# Sheet4.net
KiCad netlist of a schematic drawn in Altium Designer
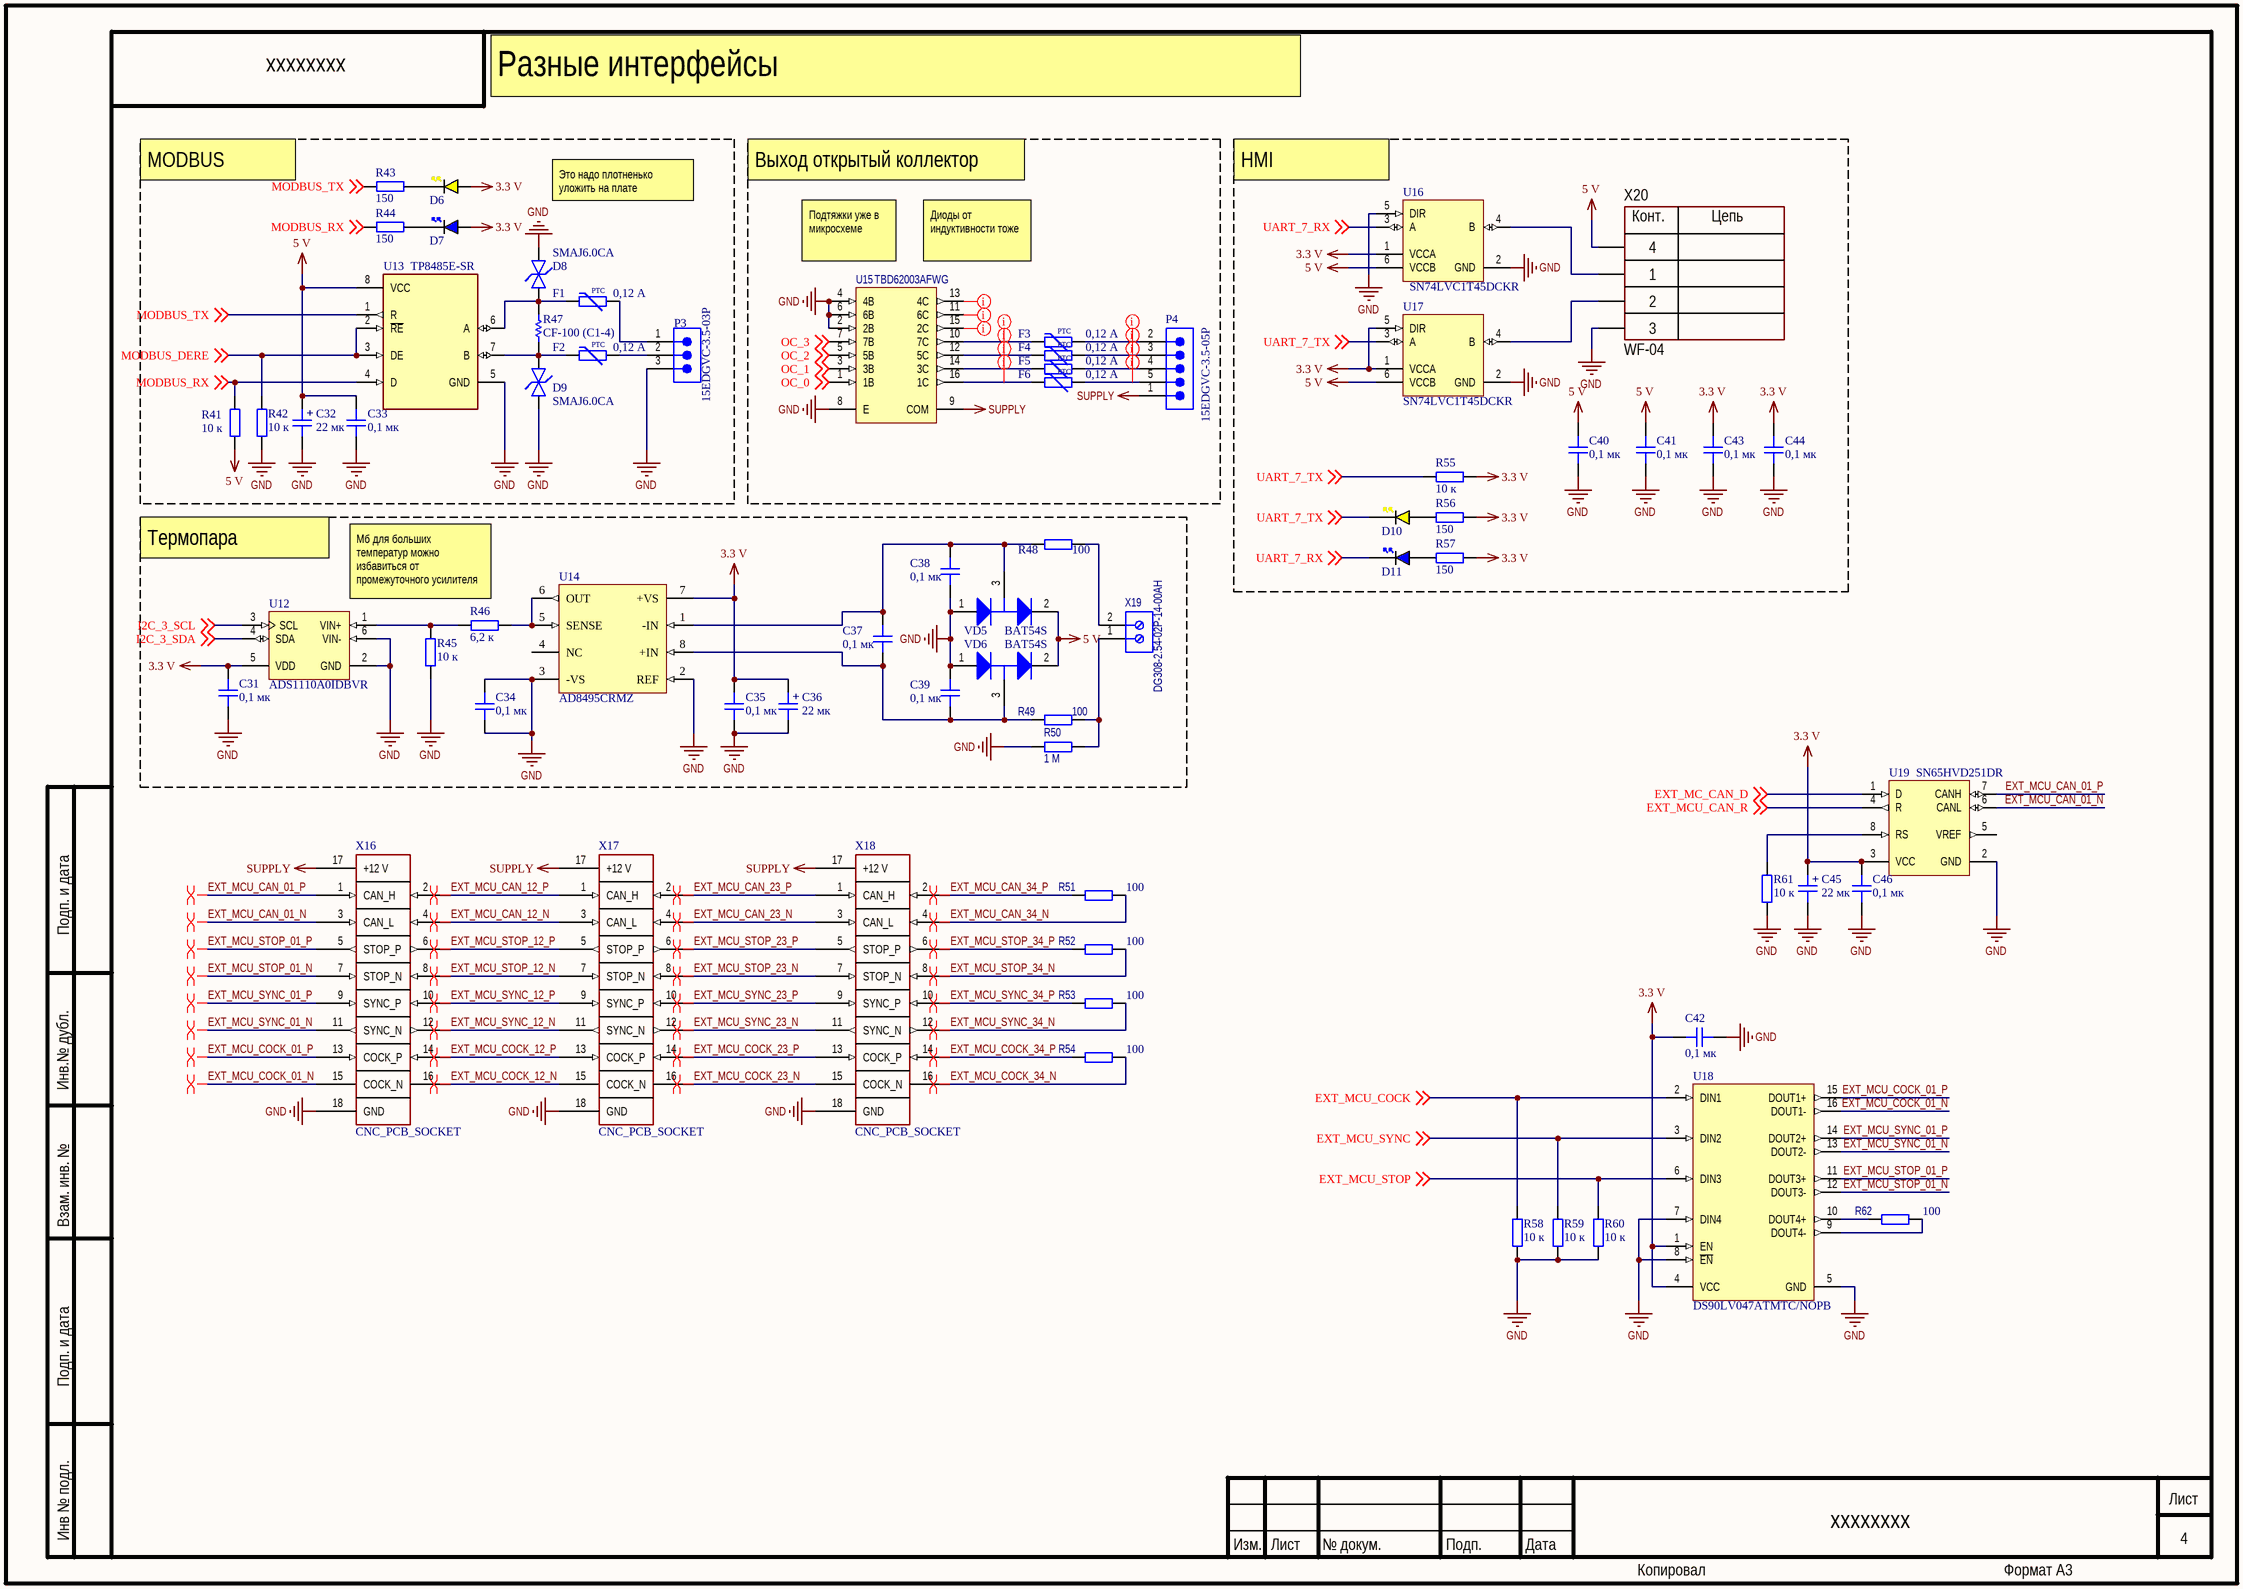
[diagram p0: Sheet4.SchDoc]

(export (version "E")
  (design (tool "Eeschema 10.0.6"))
  (components
    (comp (ref "C31")
      (value "0,1 мк")
      (footprint "CAP_0603")
      (description "Керамический конденсатор")
      (libsource (lib "Schematic-Lib-PhilsLab") (part "CAP_0603"))
    )
    (comp (ref "C32")
      (value "22 мк")
      (footprint "TANTAL_B")
      (description "Танталовый конденсатор")
      (fields (field (name "VOLTAGE") "6,3"))
      (libsource (lib "Schematic-Lib-PhilsLab") (part "CAP_ALEL_16x16.5_25V"))
    )
    (comp (ref "C33")
      (value "0,1 мк")
      (footprint "CAP_0603")
      (description "Керамический конденсатор")
      (libsource (lib "Schematic-Lib-PhilsLab") (part "CAP_0603"))
    )
    (comp (ref "C34")
      (value "0,1 мк")
      (footprint "CAP_0603")
      (description "Керамический конденсатор")
      (libsource (lib "Schematic-Lib-PhilsLab") (part "CAP_0603"))
    )
    (comp (ref "C35")
      (value "0,1 мк")
      (footprint "CAP_0603")
      (description "Керамический конденсатор")
      (libsource (lib "Schematic-Lib-PhilsLab") (part "CAP_0603"))
    )
    (comp (ref "C36")
      (value "22 мк")
      (footprint "TANTAL_B")
      (description "Танталовый конденсатор")
      (fields (field (name "VOLTAGE") "6,3"))
      (libsource (lib "Schematic-Lib-PhilsLab") (part "CAP_ALEL_16x16.5_25V"))
    )
    (comp (ref "C37")
      (value "0,1 мк")
      (footprint "CAP_0603")
      (description "Керамический конденсатор")
      (libsource (lib "Schematic-Lib-PhilsLab") (part "CAP_0603"))
    )
    (comp (ref "C38")
      (value "0,1 мк")
      (footprint "CAP_0603")
      (description "Керамический конденсатор")
      (libsource (lib "Schematic-Lib-PhilsLab") (part "CAP_0603"))
    )
    (comp (ref "C39")
      (value "0,1 мк")
      (footprint "CAP_0603")
      (description "Керамический конденсатор")
      (libsource (lib "Schematic-Lib-PhilsLab") (part "CAP_0603"))
    )
    (comp (ref "C40")
      (value "0,1 мк")
      (footprint "CAP_0603")
      (description "Керамический конденсатор")
      (libsource (lib "Schematic-Lib-PhilsLab") (part "CAP_0603"))
    )
    (comp (ref "C41")
      (value "0,1 мк")
      (footprint "CAP_0603")
      (description "Керамический конденсатор")
      (libsource (lib "Schematic-Lib-PhilsLab") (part "CAP_0603"))
    )
    (comp (ref "C42")
      (value "0,1 мк")
      (footprint "CAP_0603")
      (description "Керамический конденсатор")
      (libsource (lib "Schematic-Lib-PhilsLab") (part "CAP_0603"))
    )
    (comp (ref "C43")
      (value "0,1 мк")
      (footprint "CAP_0603")
      (description "Керамический конденсатор")
      (libsource (lib "Schematic-Lib-PhilsLab") (part "CAP_0603"))
    )
    (comp (ref "C44")
      (value "0,1 мк")
      (footprint "CAP_0603")
      (description "Керамический конденсатор")
      (libsource (lib "Schematic-Lib-PhilsLab") (part "CAP_0603"))
    )
    (comp (ref "C45")
      (value "22 мк")
      (footprint "TANTAL_B")
      (description "Танталовый конденсатор")
      (fields (field (name "VOLTAGE") "6,3"))
      (libsource (lib "Schematic-Lib-PhilsLab") (part "CAP_ALEL_16x16.5_25V"))
    )
    (comp (ref "C46")
      (value "0,1 мк")
      (footprint "CAP_0603")
      (description "Керамический конденсатор")
      (libsource (lib "Schematic-Lib-PhilsLab") (part "CAP_0603"))
    )
    (comp (ref "D6")
      (value "YELLOW")
      (footprint "LED_0603_YELLOW")
      (description "Жёлтый светодиод")
      (libsource (lib "Schematic-Lib-PhilsLab") (part "LED_0603_YELLOW"))
    )
    (comp (ref "D7")
      (value "BLUE")
      (footprint "LED_0603_BLUE")
      (description "Синий светодиод")
      (libsource (lib "Schematic-Lib-PhilsLab") (part "LED_0805_BLUE"))
    )
    (comp (ref "D8")
      (value "SMAJ6.0CA")
      (footprint "SMA")
      (description "Защитный диод")
      (libsource (lib "Schematic-Lib-PhilsLab") (part "D_TVS_BI_SMC"))
    )
    (comp (ref "D9")
      (value "SMAJ6.0CA")
      (footprint "SMA")
      (description "Защитный диод")
      (libsource (lib "Schematic-Lib-PhilsLab") (part "D_TVS_BI_SMC"))
    )
    (comp (ref "D10")
      (value "YELLOW")
      (footprint "LED_0603_YELLOW")
      (description "Жёлтый светодиод")
      (libsource (lib "Schematic-Lib-PhilsLab") (part "LED_0603_YELLOW"))
    )
    (comp (ref "D11")
      (value "BLUE")
      (footprint "LED_0603_BLUE")
      (description "Синий светодиод")
      (libsource (lib "Schematic-Lib-PhilsLab") (part "LED_0805_BLUE"))
    )
    (comp (ref "F1")
      (value "0,12 А")
      (footprint "FUSE_1206")
      (description "Самовосстанавливающийся предохранитель")
      (libsource (lib "Schematic-Lib-PhilsLab") (part "FUSE_PPTC_1206"))
    )
    (comp (ref "F2")
      (value "0,12 А")
      (footprint "FUSE_1206")
      (description "Самовосстанавливающийся предохранитель")
      (libsource (lib "Schematic-Lib-PhilsLab") (part "FUSE_PPTC_1206"))
    )
    (comp (ref "F3")
      (value "0,12 А")
      (footprint "FUSE_1206")
      (description "Самовосстанавливающийся предохранитель")
      (libsource (lib "Schematic-Lib-PhilsLab") (part "FUSE_PPTC_1206"))
    )
    (comp (ref "F4")
      (value "0,12 А")
      (footprint "FUSE_1206")
      (description "Самовосстанавливающийся предохранитель")
      (libsource (lib "Schematic-Lib-PhilsLab") (part "FUSE_PPTC_1206"))
    )
    (comp (ref "F5")
      (value "0,12 А")
      (footprint "FUSE_1206")
      (description "Самовосстанавливающийся предохранитель")
      (libsource (lib "Schematic-Lib-PhilsLab") (part "FUSE_PPTC_1206"))
    )
    (comp (ref "F6")
      (value "0,12 А")
      (footprint "FUSE_1206")
      (description "Самовосстанавливающийся предохранитель")
      (libsource (lib "Schematic-Lib-PhilsLab") (part "FUSE_PPTC_1206"))
    )
    (comp (ref "P3")
      (value "15EDGVC-3.5-03P")
      (footprint "691321100003")
      (description "Винтовой клеммник")
      (libsource (lib "Altium Content Vault") (part "TBL - 1R - 03P - Male"))
    )
    (comp (ref "P4")
      (value "15EDGVC-3.5-05P")
      (footprint "691321100005")
      (description "Винтовой клеммник")
      (libsource (lib "Altium Content Vault") (part "TBL - 1R - 05P - Male"))
    )
    (comp (ref "R41")
      (value "10 к")
      (footprint "RES_0603")
      (description "Резистор")
      (libsource (lib "Schematic-Lib-PhilsLab") (part "RES_0603"))
    )
    (comp (ref "R42")
      (value "10 к")
      (footprint "RES_0603")
      (description "Резистор")
      (libsource (lib "Schematic-Lib-PhilsLab") (part "RES_0603"))
    )
    (comp (ref "R43")
      (value "150")
      (footprint "RES_0603")
      (description "Резистор")
      (libsource (lib "Schematic-Lib-PhilsLab") (part "RES_0603"))
    )
    (comp (ref "R44")
      (value "150")
      (footprint "RES_0603")
      (description "Резистор")
      (libsource (lib "Schematic-Lib-PhilsLab") (part "RES_0603"))
    )
    (comp (ref "R45")
      (value "10 к")
      (footprint "RES_0603")
      (description "Резистор")
      (libsource (lib "Schematic-Lib-PhilsLab") (part "RES_0603"))
    )
    (comp (ref "R46")
      (value "6,2 к")
      (footprint "RES_0603")
      (description "Резистор")
      (libsource (lib "Schematic-Lib-PhilsLab") (part "RES_0603"))
    )
    (comp (ref "R47")
      (value "CF-100 (С1-4)")
      (footprint "OMTE-RES7X2.5-2")
      (description "Резистор")
      (libsource (lib "Altium Content Vault") (part "RES-2"))
    )
    (comp (ref "R48")
      (value "100")
      (footprint "RES_0603")
      (description "Резистор")
      (libsource (lib "Schematic-Lib-PhilsLab") (part "RES_0603"))
    )
    (comp (ref "R49")
      (value "100")
      (footprint "RES_0603")
      (description "Резистор")
      (libsource (lib "Schematic-Lib-PhilsLab") (part "RES_0603"))
    )
    (comp (ref "R50")
      (value "1 М")
      (footprint "RES_0603")
      (description "Резистор")
      (libsource (lib "Schematic-Lib-PhilsLab") (part "RES_0603"))
    )
    (comp (ref "R51")
      (value "100")
      (footprint "RES_0603")
      (description "Резистор")
      (libsource (lib "Schematic-Lib-PhilsLab") (part "RES_0603"))
    )
    (comp (ref "R52")
      (value "100")
      (footprint "RES_0603")
      (description "Резистор")
      (libsource (lib "Schematic-Lib-PhilsLab") (part "RES_0603"))
    )
    (comp (ref "R53")
      (value "100")
      (footprint "RES_0603")
      (description "Резистор")
      (libsource (lib "Schematic-Lib-PhilsLab") (part "RES_0603"))
    )
    (comp (ref "R54")
      (value "100")
      (footprint "RES_0603")
      (description "Резистор")
      (libsource (lib "Schematic-Lib-PhilsLab") (part "RES_0603"))
    )
    (comp (ref "R55")
      (value "10 к")
      (footprint "RES_0603")
      (description "Резистор")
      (libsource (lib "Schematic-Lib-PhilsLab") (part "RES_0603"))
    )
    (comp (ref "R56")
      (value "150")
      (footprint "RES_0603")
      (description "Резистор")
      (libsource (lib "Schematic-Lib-PhilsLab") (part "RES_0603"))
    )
    (comp (ref "R57")
      (value "150")
      (footprint "RES_0603")
      (description "Резистор")
      (libsource (lib "Schematic-Lib-PhilsLab") (part "RES_0603"))
    )
    (comp (ref "R58")
      (value "10 к")
      (footprint "RES_0603")
      (description "Резистор")
      (libsource (lib "Schematic-Lib-PhilsLab") (part "RES_0603"))
    )
    (comp (ref "R59")
      (value "10 к")
      (footprint "RES_0603")
      (description "Резистор")
      (libsource (lib "Schematic-Lib-PhilsLab") (part "RES_0603"))
    )
    (comp (ref "R60")
      (value "10 к")
      (footprint "RES_0603")
      (description "Резистор")
      (libsource (lib "Schematic-Lib-PhilsLab") (part "RES_0603"))
    )
    (comp (ref "R61")
      (value "10 к")
      (footprint "RES_0603")
      (description "Резистор")
      (libsource (lib "Schematic-Lib-PhilsLab") (part "RES_0603"))
    )
    (comp (ref "R62")
      (value "100")
      (footprint "RES_0603")
      (description "Резистор")
      (libsource (lib "Schematic-Lib-PhilsLab") (part "RES_0603"))
    )
    (comp (ref "U12")
      (value "ADS1110A0IDBVR")
      (footprint "TI-DBV6_M")
      (description "АЦП с I2C")
      (libsource (lib "Altium Content Vault") (part "TI-ADS1XX0XDBV6"))
    )
    (comp (ref "U13")
      (value "TP8485E-SR")
      (footprint "FP-D0008A-MFG")
      (description "Конвертер UART <-> RS485")
      (libsource (lib "Altium Content Vault") (part "091f02ab22138f139970934c9fc963e"))
    )
    (comp (ref "U14")
      (value "AD8495CRMZ")
      (footprint "FP-RM-8-IPC_A")
      (description "Усилитель термопары")
      (libsource (lib "Altium Content Vault") (part "AD8495CRMZ"))
    )
    (comp (ref "U15")
      (value "TBD62003AFWG")
      (footprint "D0016A_M")
      (description "Сборка транзисторов Дарлингтона")
      (libsource (lib "Altium Content Vault") (part "TI-ULX200X-D-16"))
    )
    (comp (ref "U16")
      (value "SN74LVC1T45DCKR")
      (footprint "DCK0006A_L")
      (description "Конвертер уровней")
      (libsource (lib "Altium Content Vault") (part "TI-SN74XVC1T45-6"))
    )
    (comp (ref "U17")
      (value "SN74LVC1T45DCKR")
      (footprint "DCK0006A_L")
      (description "Конвертер уровней")
      (libsource (lib "Altium Content Vault") (part "TI-SN74XVC1T45-6"))
    )
    (comp (ref "U18")
      (value "DS90LV047ATMTC/NOPB")
      (footprint "MTC16_M")
      (description "Драйвер LVDS")
      (libsource (lib "Altium Content Vault") (part "IN-LNDRV-DS90LV047ATM"))
    )
    (comp (ref "U19")
      (value "SN65HVD251DR")
      (footprint "D0008A_N")
      (description "Драйвер CAN")
      (libsource (lib "Altium Content Vault") (part "TI-SN65HVD251-SOIC_D-8"))
    )
    (comp (ref "VD5")
      (value "BAT54S")
      (footprint "ONSC-SOT-323-3-419-04_V")
      (description "Пара последовательных диодов")
      (libsource (lib "Altium Content Vault") (part "ONSC-D-A1K2C3-3"))
    )
    (comp (ref "VD6")
      (value "BAT54S")
      (footprint "ONSC-SOT-323-3-419-04_V")
      (description "Пара последовательных диодов")
      (libsource (lib "Altium Content Vault") (part "ONSC-D-A1K2C3-3"))
    )
    (comp (ref "X16")
      (value "CNC_PCB_SOCKET")
      (footprint "CNC_PCB_SOCKET")
      (libsource (lib "BarkockLib") (part "CNC_PCB_SOCKET"))
    )
    (comp (ref "X17")
      (value "CNC_PCB_SOCKET")
      (footprint "CNC_PCB_SOCKET")
      (libsource (lib "BarkockLib") (part "CNC_PCB_SOCKET"))
    )
    (comp (ref "X18")
      (value "CNC_PCB_SOCKET")
      (footprint "CNC_PCB_SOCKET")
      (libsource (lib "BarkockLib") (part "CNC_PCB_SOCKET"))
    )
    (comp (ref "X19")
      (value "DG308-2.54-02P-14-00AH")
      (footprint "PHOE-1725656-2")
      (description "Рахъёмный винтовой клеммник")
      (libsource (lib "Altium Content Vault") (part "CN-1P-F-TB2"))
    )
    (comp (ref "X20")
      (value "WF-04")
      (footprint "CON: WF-04")
      (description "Штыревой разъём")
      (libsource (lib "Connectors") (part "4-Connector"))
    )
  )
  (nets
    (net (code "1") (name "/EXT_MCU_CAN_01_N") (class "Default")
      (node (ref "U19") (pin "6") (pinfunction "CANL_6") (pintype "bidirectional"))
      (node (ref "X16") (pin "3") (pinfunction "CAN_L_3") (pintype "input"))
    )
    (net (code "2") (name "/EXT_MCU_CAN_01_P") (class "Default")
      (node (ref "U19") (pin "7") (pinfunction "CANH_7") (pintype "bidirectional"))
      (node (ref "X16") (pin "1") (pinfunction "CAN_H_1") (pintype "input"))
    )
    (net (code "3") (name "/EXT_MCU_CAN_12_N") (class "Default")
      (node (ref "X16") (pin "4") (pinfunction "CAN_L_4") (pintype "input"))
      (node (ref "X17") (pin "3") (pinfunction "CAN_L_3") (pintype "input"))
    )
    (net (code "4") (name "/EXT_MCU_CAN_12_P") (class "Default")
      (node (ref "X16") (pin "2") (pinfunction "CAN_H_2") (pintype "input"))
      (node (ref "X17") (pin "1") (pinfunction "CAN_H_1") (pintype "input"))
    )
    (net (code "5") (name "/EXT_MCU_CAN_23_N") (class "Default")
      (node (ref "X17") (pin "4") (pinfunction "CAN_L_4") (pintype "input"))
      (node (ref "X18") (pin "3") (pinfunction "CAN_L_3") (pintype "input"))
    )
    (net (code "6") (name "/EXT_MCU_CAN_23_P") (class "Default")
      (node (ref "X17") (pin "2") (pinfunction "CAN_H_2") (pintype "input"))
      (node (ref "X18") (pin "1") (pinfunction "CAN_H_1") (pintype "input"))
    )
    (net (code "7") (name "/EXT_MCU_CAN_34_N") (class "Default")
      (node (ref "R51") (pin "1") (pinfunction "1_1") (pintype "passive"))
      (node (ref "X18") (pin "4") (pinfunction "CAN_L_4") (pintype "input"))
    )
    (net (code "8") (name "/EXT_MCU_CAN_34_P") (class "Default")
      (node (ref "R51") (pin "2") (pinfunction "2_2") (pintype "passive"))
      (node (ref "X18") (pin "2") (pinfunction "CAN_H_2") (pintype "input"))
    )
    (net (code "9") (name "/EXT_MCU_COCK_01_N") (class "Default")
      (node (ref "U18") (pin "16") (pinfunction "DOUT1-_16") (pintype "output"))
      (node (ref "X16") (pin "15") (pinfunction "COCK_N_15") (pintype "power_in"))
    )
    (net (code "10") (name "/EXT_MCU_COCK_01_P") (class "Default")
      (node (ref "U18") (pin "15") (pinfunction "DOUT1+_15") (pintype "output"))
      (node (ref "X16") (pin "13") (pinfunction "COCK_P_13") (pintype "input"))
    )
    (net (code "11") (name "/EXT_MCU_COCK_12_N") (class "Default")
      (node (ref "X16") (pin "16") (pinfunction "COCK_N_16") (pintype "power_in"))
      (node (ref "X17") (pin "15") (pinfunction "COCK_N_15") (pintype "power_in"))
    )
    (net (code "12") (name "/EXT_MCU_COCK_12_P") (class "Default")
      (node (ref "X16") (pin "14") (pinfunction "COCK_P_14") (pintype "input"))
      (node (ref "X17") (pin "13") (pinfunction "COCK_P_13") (pintype "input"))
    )
    (net (code "13") (name "/EXT_MCU_COCK_23_N") (class "Default")
      (node (ref "X17") (pin "16") (pinfunction "COCK_N_16") (pintype "power_in"))
      (node (ref "X18") (pin "15") (pinfunction "COCK_N_15") (pintype "power_in"))
    )
    (net (code "14") (name "/EXT_MCU_COCK_23_P") (class "Default")
      (node (ref "X17") (pin "14") (pinfunction "COCK_P_14") (pintype "input"))
      (node (ref "X18") (pin "13") (pinfunction "COCK_P_13") (pintype "input"))
    )
    (net (code "15") (name "/EXT_MCU_COCK_34_N") (class "Default")
      (node (ref "R54") (pin "1") (pinfunction "1_1") (pintype "passive"))
      (node (ref "X18") (pin "16") (pinfunction "COCK_N_16") (pintype "power_in"))
    )
    (net (code "16") (name "/EXT_MCU_COCK_34_P") (class "Default")
      (node (ref "R54") (pin "2") (pinfunction "2_2") (pintype "passive"))
      (node (ref "X18") (pin "14") (pinfunction "COCK_P_14") (pintype "input"))
    )
    (net (code "17") (name "/EXT_MCU_STOP_01_N") (class "Default")
      (node (ref "U18") (pin "12") (pinfunction "DOUT3-_12") (pintype "output"))
      (node (ref "X16") (pin "7") (pinfunction "STOP_N_7") (pintype "input"))
    )
    (net (code "18") (name "/EXT_MCU_STOP_01_P") (class "Default")
      (node (ref "U18") (pin "11") (pinfunction "DOUT3+_11") (pintype "output"))
      (node (ref "X16") (pin "5") (pinfunction "STOP_P_5") (pintype "output"))
    )
    (net (code "19") (name "/EXT_MCU_STOP_12_N") (class "Default")
      (node (ref "X16") (pin "8") (pinfunction "STOP_N_8") (pintype "input"))
      (node (ref "X17") (pin "7") (pinfunction "STOP_N_7") (pintype "input"))
    )
    (net (code "20") (name "/EXT_MCU_STOP_12_P") (class "Default")
      (node (ref "X16") (pin "6") (pinfunction "STOP_P_6") (pintype "output"))
      (node (ref "X17") (pin "5") (pinfunction "STOP_P_5") (pintype "output"))
    )
    (net (code "21") (name "/EXT_MCU_STOP_23_N") (class "Default")
      (node (ref "X17") (pin "8") (pinfunction "STOP_N_8") (pintype "input"))
      (node (ref "X18") (pin "7") (pinfunction "STOP_N_7") (pintype "input"))
    )
    (net (code "22") (name "/EXT_MCU_STOP_23_P") (class "Default")
      (node (ref "X17") (pin "6") (pinfunction "STOP_P_6") (pintype "output"))
      (node (ref "X18") (pin "5") (pinfunction "STOP_P_5") (pintype "output"))
    )
    (net (code "23") (name "/EXT_MCU_STOP_34_N") (class "Default")
      (node (ref "R52") (pin "1") (pinfunction "1_1") (pintype "passive"))
      (node (ref "X18") (pin "8") (pinfunction "STOP_N_8") (pintype "input"))
    )
    (net (code "24") (name "/EXT_MCU_STOP_34_P") (class "Default")
      (node (ref "R52") (pin "2") (pinfunction "2_2") (pintype "passive"))
      (node (ref "X18") (pin "6") (pinfunction "STOP_P_6") (pintype "output"))
    )
    (net (code "25") (name "/EXT_MCU_SYNC_01_N") (class "Default")
      (node (ref "U18") (pin "13") (pinfunction "DOUT2-_13") (pintype "output"))
      (node (ref "X16") (pin "11") (pinfunction "SYNC_N_11") (pintype "output"))
    )
    (net (code "26") (name "/EXT_MCU_SYNC_01_P") (class "Default")
      (node (ref "U18") (pin "14") (pinfunction "DOUT2+_14") (pintype "output"))
      (node (ref "X16") (pin "9") (pinfunction "SYNC_P_9") (pintype "input"))
    )
    (net (code "27") (name "/EXT_MCU_SYNC_12_N") (class "Default")
      (node (ref "X16") (pin "12") (pinfunction "SYNC_N_12") (pintype "output"))
      (node (ref "X17") (pin "11") (pinfunction "SYNC_N_11") (pintype "output"))
    )
    (net (code "28") (name "/EXT_MCU_SYNC_12_P") (class "Default")
      (node (ref "X16") (pin "10") (pinfunction "SYNC_P_10") (pintype "input"))
      (node (ref "X17") (pin "9") (pinfunction "SYNC_P_9") (pintype "input"))
    )
    (net (code "29") (name "/EXT_MCU_SYNC_23_N") (class "Default")
      (node (ref "X17") (pin "12") (pinfunction "SYNC_N_12") (pintype "output"))
      (node (ref "X18") (pin "11") (pinfunction "SYNC_N_11") (pintype "output"))
    )
    (net (code "30") (name "/EXT_MCU_SYNC_23_P") (class "Default")
      (node (ref "X17") (pin "10") (pinfunction "SYNC_P_10") (pintype "input"))
      (node (ref "X18") (pin "9") (pinfunction "SYNC_P_9") (pintype "input"))
    )
    (net (code "31") (name "/EXT_MCU_SYNC_34_N") (class "Default")
      (node (ref "R53") (pin "1") (pinfunction "1_1") (pintype "passive"))
      (node (ref "X18") (pin "12") (pinfunction "SYNC_N_12") (pintype "output"))
    )
    (net (code "32") (name "/EXT_MCU_SYNC_34_P") (class "Default")
      (node (ref "R53") (pin "2") (pinfunction "2_2") (pintype "passive"))
      (node (ref "X18") (pin "10") (pinfunction "SYNC_P_10") (pintype "input"))
    )
    (net (code "33") (name "3.3 V") (class "Default")
      (node (ref "C31") (pin "1") (pinfunction "1_1") (pintype "passive"))
      (node (ref "C35") (pin "1") (pinfunction "1_1") (pintype "passive"))
      (node (ref "C36") (pin "1") (pinfunction "1_1") (pintype "passive"))
      (node (ref "C42") (pin "1") (pinfunction "1_1") (pintype "passive"))
      (node (ref "C43") (pin "1") (pinfunction "1_1") (pintype "passive"))
      (node (ref "C44") (pin "1") (pinfunction "1_1") (pintype "passive"))
      (node (ref "C45") (pin "1") (pinfunction "1_1") (pintype "passive"))
      (node (ref "C46") (pin "1") (pinfunction "1_1") (pintype "passive"))
      (node (ref "D6") (pin "A") (pinfunction "A_A") (pintype "passive"))
      (node (ref "D7") (pin "A") (pinfunction "A_A") (pintype "passive"))
      (node (ref "R55") (pin "1") (pinfunction "1_1") (pintype "passive"))
      (node (ref "R56") (pin "2") (pinfunction "2_2") (pintype "passive"))
      (node (ref "R57") (pin "2") (pinfunction "2_2") (pintype "passive"))
      (node (ref "U12") (pin "5") (pinfunction "VDD_5") (pintype "power_in"))
      (node (ref "U14") (pin "7") (pinfunction "+VS_7") (pintype "power_in"))
      (node (ref "U16") (pin "1") (pinfunction "VCCA_1") (pintype "power_in"))
      (node (ref "U17") (pin "1") (pinfunction "VCCA_1") (pintype "power_in"))
      (node (ref "U17") (pin "5") (pinfunction "DIR_5") (pintype "input"))
      (node (ref "U18") (pin "1") (pinfunction "EN_1") (pintype "input"))
      (node (ref "U18") (pin "4") (pinfunction "VCC_4") (pintype "power_in"))
      (node (ref "U19") (pin "3") (pinfunction "VCC_3") (pintype "power_in"))
    )
    (net (code "34") (name "5 V") (class "Default")
      (node (ref "C32") (pin "1") (pinfunction "1_1") (pintype "passive"))
      (node (ref "C33") (pin "1") (pinfunction "1_1") (pintype "passive"))
      (node (ref "C40") (pin "1") (pinfunction "1_1") (pintype "passive"))
      (node (ref "C41") (pin "1") (pinfunction "1_1") (pintype "passive"))
      (node (ref "R41") (pin "2") (pinfunction "2_2") (pintype "passive"))
      (node (ref "U13") (pin "8") (pinfunction "VCC_8") (pintype "power_in"))
      (node (ref "U16") (pin "6") (pinfunction "VCCB_6") (pintype "power_in"))
      (node (ref "U17") (pin "6") (pinfunction "VCCB_6") (pintype "power_in"))
      (node (ref "VD5") (pin "2") (pinfunction "K_2") (pintype "passive"))
      (node (ref "VD6") (pin "2") (pinfunction "K_2") (pintype "passive"))
      (node (ref "X20") (pin "4") (pinfunction "4_4") (pintype "passive"))
    )
    (net (code "35") (name "EXT_MCU_CAN_R") (class "Default")
      (node (ref "U19") (pin "4") (pinfunction "R_4") (pintype "output"))
    )
    (net (code "36") (name "EXT_MCU_COCK") (class "Default")
      (node (ref "R58") (pin "1") (pinfunction "1_1") (pintype "passive"))
      (node (ref "U18") (pin "2") (pinfunction "DIN1_2") (pintype "input"))
    )
    (net (code "37") (name "EXT_MCU_STOP") (class "Default")
      (node (ref "R60") (pin "2") (pinfunction "2_2") (pintype "passive"))
      (node (ref "U18") (pin "6") (pinfunction "DIN3_6") (pintype "input"))
    )
    (net (code "38") (name "EXT_MCU_SYNC") (class "Default")
      (node (ref "R59") (pin "1") (pinfunction "1_1") (pintype "passive"))
      (node (ref "U18") (pin "3") (pinfunction "DIN2_3") (pintype "input"))
    )
    (net (code "39") (name "EXT_MC_CAN_D") (class "Default")
      (node (ref "U19") (pin "1") (pinfunction "D_1") (pintype "input"))
    )
    (net (code "40") (name "GND") (class "Default")
      (node (ref "C31") (pin "2") (pinfunction "2_2") (pintype "passive"))
      (node (ref "C32") (pin "2") (pinfunction "2_2") (pintype "passive"))
      (node (ref "C33") (pin "2") (pinfunction "2_2") (pintype "passive"))
      (node (ref "C34") (pin "1") (pinfunction "1_1") (pintype "passive"))
      (node (ref "C34") (pin "2") (pinfunction "2_2") (pintype "passive"))
      (node (ref "C35") (pin "2") (pinfunction "2_2") (pintype "passive"))
      (node (ref "C36") (pin "2") (pinfunction "2_2") (pintype "passive"))
      (node (ref "C38") (pin "2") (pinfunction "2_2") (pintype "passive"))
      (node (ref "C39") (pin "1") (pinfunction "1_1") (pintype "passive"))
      (node (ref "C40") (pin "2") (pinfunction "2_2") (pintype "passive"))
      (node (ref "C41") (pin "2") (pinfunction "2_2") (pintype "passive"))
      (node (ref "C42") (pin "2") (pinfunction "2_2") (pintype "passive"))
      (node (ref "C43") (pin "2") (pinfunction "2_2") (pintype "passive"))
      (node (ref "C44") (pin "2") (pinfunction "2_2") (pintype "passive"))
      (node (ref "C45") (pin "2") (pinfunction "2_2") (pintype "passive"))
      (node (ref "C46") (pin "2") (pinfunction "2_2") (pintype "passive"))
      (node (ref "D8") (pin "K") (pinfunction "K_K") (pintype "passive"))
      (node (ref "D9") (pin "A") (pinfunction "A_A") (pintype "passive"))
      (node (ref "P3") (pin "3") (pinfunction "3_3") (pintype "passive"))
      (node (ref "R42") (pin "1") (pinfunction "1_1") (pintype "passive"))
      (node (ref "R45") (pin "1") (pinfunction "1_1") (pintype "passive"))
      (node (ref "R50") (pin "2") (pinfunction "2_2") (pintype "passive"))
      (node (ref "R58") (pin "2") (pinfunction "2_2") (pintype "passive"))
      (node (ref "R59") (pin "2") (pinfunction "2_2") (pintype "passive"))
      (node (ref "R60") (pin "1") (pinfunction "1_1") (pintype "passive"))
      (node (ref "R61") (pin "1") (pinfunction "1_1") (pintype "passive"))
      (node (ref "U12") (pin "2") (pinfunction "GND_2") (pintype "power_in"))
      (node (ref "U12") (pin "6") (pinfunction "VIN-_6") (pintype "input"))
      (node (ref "U13") (pin "5") (pinfunction "GND_5") (pintype "power_in"))
      (node (ref "U14") (pin "2") (pinfunction "REF_2") (pintype "input"))
      (node (ref "U14") (pin "3") (pinfunction "-VS_3") (pintype "power_in"))
      (node (ref "U15") (pin "2") (pinfunction "2B_2") (pintype "input"))
      (node (ref "U15") (pin "4") (pinfunction "4B_4") (pintype "input"))
      (node (ref "U15") (pin "6") (pinfunction "6B_6") (pintype "input"))
      (node (ref "U15") (pin "8") (pinfunction "E_8") (pintype "passive"))
      (node (ref "U16") (pin "2") (pinfunction "GND_2") (pintype "power_in"))
      (node (ref "U16") (pin "5") (pinfunction "DIR_5") (pintype "input"))
      (node (ref "U17") (pin "2") (pinfunction "GND_2") (pintype "power_in"))
      (node (ref "U18") (pin "5") (pinfunction "GND_5") (pintype "power_in"))
      (node (ref "U18") (pin "7") (pinfunction "DIN4_7") (pintype "input"))
      (node (ref "U18") (pin "8") (pinfunction "~{EN}_8") (pintype "input"))
      (node (ref "U19") (pin "2") (pinfunction "GND_2") (pintype "power_in"))
      (node (ref "VD5") (pin "1") (pinfunction "A_1") (pintype "passive"))
      (node (ref "VD6") (pin "1") (pinfunction "A_1") (pintype "passive"))
      (node (ref "X16") (pin "18") (pinfunction "GND_18") (pintype "power_in"))
      (node (ref "X17") (pin "18") (pinfunction "GND_18") (pintype "power_in"))
      (node (ref "X18") (pin "18") (pinfunction "GND_18") (pintype "power_in"))
      (node (ref "X20") (pin "3") (pinfunction "3_3") (pintype "power_in"))
    )
    (net (code "41") (name "I2C_3_SCL") (class "Default")
      (node (ref "U12") (pin "3") (pinfunction "SCL_3") (pintype "input"))
    )
    (net (code "42") (name "I2C_3_SDA") (class "Default")
      (node (ref "U12") (pin "4") (pinfunction "SDA_4") (pintype "bidirectional"))
    )
    (net (code "43") (name "MODBUS_DERE") (class "Default")
      (node (ref "R42") (pin "2") (pinfunction "2_2") (pintype "passive"))
      (node (ref "U13") (pin "2") (pinfunction "~{RE}_2") (pintype "input"))
      (node (ref "U13") (pin "3") (pinfunction "DE_3") (pintype "input"))
    )
    (net (code "44") (name "MODBUS_RX") (class "Default")
      (node (ref "R41") (pin "1") (pinfunction "1_1") (pintype "passive"))
      (node (ref "R44") (pin "1") (pinfunction "1_1") (pintype "passive"))
      (node (ref "U13") (pin "4") (pinfunction "D_4") (pintype "input"))
    )
    (net (code "45") (name "MODBUS_TX") (class "Default")
      (node (ref "R43") (pin "1") (pinfunction "1_1") (pintype "passive"))
      (node (ref "U13") (pin "1") (pinfunction "R_1") (pintype "output"))
    )
    (net (code "46") (name "Net-(D6-PadK)") (class "Default")
      (node (ref "D6") (pin "K") (pinfunction "K_K") (pintype "passive"))
      (node (ref "R43") (pin "2") (pinfunction "2_2") (pintype "passive"))
    )
    (net (code "47") (name "Net-(D7-PadK)") (class "Default")
      (node (ref "D7") (pin "K") (pinfunction "K_K") (pintype "passive"))
      (node (ref "R44") (pin "2") (pinfunction "2_2") (pintype "passive"))
    )
    (net (code "48") (name "Net-(D10-PadA)") (class "Default")
      (node (ref "D10") (pin "A") (pinfunction "A_A") (pintype "passive"))
      (node (ref "R56") (pin "1") (pinfunction "1_1") (pintype "passive"))
    )
    (net (code "49") (name "Net-(D11-PadA)") (class "Default")
      (node (ref "D11") (pin "A") (pinfunction "A_A") (pintype "passive"))
      (node (ref "R57") (pin "1") (pinfunction "1_1") (pintype "passive"))
    )
    (net (code "50") (name "Net-(F1-Pad1)") (class "Default")
      (node (ref "F1") (pin "1") (pinfunction "1_1") (pintype "passive"))
      (node (ref "P3") (pin "1") (pinfunction "1_1") (pintype "passive"))
    )
    (net (code "51") (name "Net-(F2-Pad1)") (class "Default")
      (node (ref "F2") (pin "1") (pinfunction "1_1") (pintype "passive"))
      (node (ref "P3") (pin "2") (pinfunction "2_2") (pintype "passive"))
    )
    (net (code "52") (name "Net-(F3-Pad1)") (class "Default")
      (node (ref "F3") (pin "1") (pinfunction "1_1") (pintype "passive"))
      (node (ref "P4") (pin "2") (pinfunction "2_2") (pintype "passive"))
    )
    (net (code "53") (name "Net-(F4-Pad1)") (class "Default")
      (node (ref "F4") (pin "1") (pinfunction "1_1") (pintype "passive"))
      (node (ref "P4") (pin "3") (pinfunction "3_3") (pintype "passive"))
    )
    (net (code "54") (name "Net-(F5-Pad1)") (class "Default")
      (node (ref "F5") (pin "1") (pinfunction "1_1") (pintype "passive"))
      (node (ref "P4") (pin "4") (pinfunction "4_4") (pintype "passive"))
    )
    (net (code "55") (name "Net-(F6-Pad1)") (class "Default")
      (node (ref "F6") (pin "1") (pinfunction "1_1") (pintype "passive"))
      (node (ref "P4") (pin "5") (pinfunction "5_5") (pintype "passive"))
    )
    (net (code "56") (name "Net-(R48-Pad2)") (class "Default")
      (node (ref "R48") (pin "2") (pinfunction "2_2") (pintype "passive"))
      (node (ref "X19") (pin "2") (pinfunction "2_2") (pintype "passive"))
    )
    (net (code "57") (name "Net-(R49-Pad2)") (class "Default")
      (node (ref "R49") (pin "2") (pinfunction "2_2") (pintype "passive"))
      (node (ref "R50") (pin "1") (pinfunction "1_1") (pintype "passive"))
      (node (ref "X19") (pin "1") (pinfunction "1_1") (pintype "passive"))
    )
    (net (code "58") (name "Net-(U12-VIN+)") (class "Default")
      (node (ref "R45") (pin "2") (pinfunction "2_2") (pintype "passive"))
      (node (ref "R46") (pin "2") (pinfunction "2_2") (pintype "passive"))
      (node (ref "U12") (pin "1") (pinfunction "VIN+_1") (pintype "input"))
    )
    (net (code "59") (name "Net-(U13-A)") (class "Default")
      (node (ref "D8") (pin "A") (pinfunction "A_A") (pintype "passive"))
      (node (ref "F1") (pin "2") (pinfunction "2_2") (pintype "passive"))
      (node (ref "R47") (pin "1") (pinfunction "1_1") (pintype "passive"))
      (node (ref "U13") (pin "6") (pinfunction "A_6") (pintype "bidirectional"))
    )
    (net (code "60") (name "Net-(U13-B)") (class "Default")
      (node (ref "D9") (pin "K") (pinfunction "K_K") (pintype "passive"))
      (node (ref "F2") (pin "2") (pinfunction "2_2") (pintype "passive"))
      (node (ref "R47") (pin "2") (pinfunction "2_2") (pintype "passive"))
      (node (ref "U13") (pin "7") (pinfunction "B_7") (pintype "bidirectional"))
    )
    (net (code "61") (name "Net-(U14-+IN)") (class "Default")
      (node (ref "C37") (pin "2") (pinfunction "2_2") (pintype "passive"))
      (node (ref "C39") (pin "2") (pinfunction "2_2") (pintype "passive"))
      (node (ref "R49") (pin "1") (pinfunction "1_1") (pintype "passive"))
      (node (ref "U14") (pin "8") (pinfunction "+IN_8") (pintype "input"))
      (node (ref "VD6") (pin "3") (pinfunction "K/A_3") (pintype "passive"))
    )
    (net (code "62") (name "Net-(U14--IN)") (class "Default")
      (node (ref "C37") (pin "1") (pinfunction "1_1") (pintype "passive"))
      (node (ref "C38") (pin "1") (pinfunction "1_1") (pintype "passive"))
      (node (ref "R48") (pin "1") (pinfunction "1_1") (pintype "passive"))
      (node (ref "U14") (pin "1") (pinfunction "-IN_1") (pintype "input"))
      (node (ref "VD5") (pin "3") (pinfunction "K/A_3") (pintype "passive"))
    )
    (net (code "63") (name "Net-(U14-OUT)") (class "Default")
      (node (ref "R46") (pin "1") (pinfunction "1_1") (pintype "passive"))
      (node (ref "U14") (pin "5") (pinfunction "SENSE_5") (pintype "input"))
      (node (ref "U14") (pin "6") (pinfunction "OUT_6") (pintype "output"))
    )
    (net (code "64") (name "Net-(U15-1C)") (class "Default")
      (node (ref "F6") (pin "2") (pinfunction "2_2") (pintype "passive"))
      (node (ref "U15") (pin "16") (pinfunction "1C_16") (pintype "output"))
    )
    (net (code "65") (name "Net-(U15-3C)") (class "Default")
      (node (ref "F5") (pin "2") (pinfunction "2_2") (pintype "passive"))
      (node (ref "U15") (pin "14") (pinfunction "3C_14") (pintype "output"))
    )
    (net (code "66") (name "Net-(U15-5C)") (class "Default")
      (node (ref "F4") (pin "2") (pinfunction "2_2") (pintype "passive"))
      (node (ref "U15") (pin "12") (pinfunction "5C_12") (pintype "output"))
    )
    (net (code "67") (name "Net-(U15-7C)") (class "Default")
      (node (ref "F3") (pin "2") (pinfunction "2_2") (pintype "passive"))
      (node (ref "U15") (pin "10") (pinfunction "7C_10") (pintype "output"))
    )
    (net (code "68") (name "Net-(U16-B)") (class "Default")
      (node (ref "U16") (pin "4") (pinfunction "B_4") (pintype "bidirectional"))
      (node (ref "X20") (pin "1") (pinfunction "1_1") (pintype "passive"))
    )
    (net (code "69") (name "Net-(U17-B)") (class "Default")
      (node (ref "U17") (pin "4") (pinfunction "B_4") (pintype "bidirectional"))
      (node (ref "X20") (pin "2") (pinfunction "2_2") (pintype "power_in"))
    )
    (net (code "70") (name "Net-(U18-DOUT4+)") (class "Default")
      (node (ref "R62") (pin "2") (pinfunction "2_2") (pintype "passive"))
      (node (ref "U18") (pin "10") (pinfunction "DOUT4+_10") (pintype "output"))
    )
    (net (code "71") (name "Net-(U18-DOUT4-)") (class "Default")
      (node (ref "R62") (pin "1") (pinfunction "1_1") (pintype "passive"))
      (node (ref "U18") (pin "9") (pinfunction "DOUT4-_9") (pintype "output"))
    )
    (net (code "72") (name "Net-(U19-RS)") (class "Default")
      (node (ref "R61") (pin "2") (pinfunction "2_2") (pintype "passive"))
      (node (ref "U19") (pin "8") (pinfunction "RS_8") (pintype "input"))
    )
    (net (code "73") (name "OС_0") (class "Default")
      (node (ref "U15") (pin "1") (pinfunction "1B_1") (pintype "input"))
    )
    (net (code "74") (name "OС_1") (class "Default")
      (node (ref "U15") (pin "3") (pinfunction "3B_3") (pintype "input"))
    )
    (net (code "75") (name "OС_2") (class "Default")
      (node (ref "U15") (pin "5") (pinfunction "5B_5") (pintype "input"))
    )
    (net (code "76") (name "OС_3") (class "Default")
      (node (ref "U15") (pin "7") (pinfunction "7B_7") (pintype "input"))
    )
    (net (code "77") (name "SUPPLY") (class "Default")
      (node (ref "P4") (pin "1") (pinfunction "1_1") (pintype "passive"))
      (node (ref "U15") (pin "9") (pinfunction "COM_9") (pintype "passive"))
      (node (ref "X16") (pin "17") (pinfunction "+12_V_17") (pintype "power_in"))
      (node (ref "X17") (pin "17") (pinfunction "+12_V_17") (pintype "power_in"))
      (node (ref "X18") (pin "17") (pinfunction "+12_V_17") (pintype "power_in"))
    )
    (net (code "78") (name "UART_7_RX") (class "Default")
      (node (ref "D11") (pin "K") (pinfunction "K_K") (pintype "passive"))
      (node (ref "U16") (pin "3") (pinfunction "A_3") (pintype "bidirectional"))
    )
    (net (code "79") (name "UART_7_TX") (class "Default")
      (node (ref "D10") (pin "K") (pinfunction "K_K") (pintype "passive"))
      (node (ref "R55") (pin "2") (pinfunction "2_2") (pintype "passive"))
      (node (ref "U17") (pin "3") (pinfunction "A_3") (pintype "bidirectional"))
    )
    (net (code "80") (name "unconnected-(U14-NC-Pad4)") (class "Default")
      (node (ref "U14") (pin "4") (pinfunction "NC_4") (pintype "passive"))
    )
    (net (code "81") (name "unconnected-(U15-2C-Pad15)") (class "Default")
      (node (ref "U15") (pin "15") (pinfunction "2C_15") (pintype "output"))
    )
    (net (code "82") (name "unconnected-(U15-4C-Pad13)") (class "Default")
      (node (ref "U15") (pin "13") (pinfunction "4C_13") (pintype "output"))
    )
    (net (code "83") (name "unconnected-(U15-6C-Pad11)") (class "Default")
      (node (ref "U15") (pin "11") (pinfunction "6C_11") (pintype "output"))
    )
    (net (code "84") (name "unconnected-(U19-VREF-Pad5)") (class "Default")
      (node (ref "U19") (pin "5") (pinfunction "VREF_5") (pintype "output"))
    )
  )
)
